# DAC.net
KiCad netlist of a schematic drawn in Altium Designer
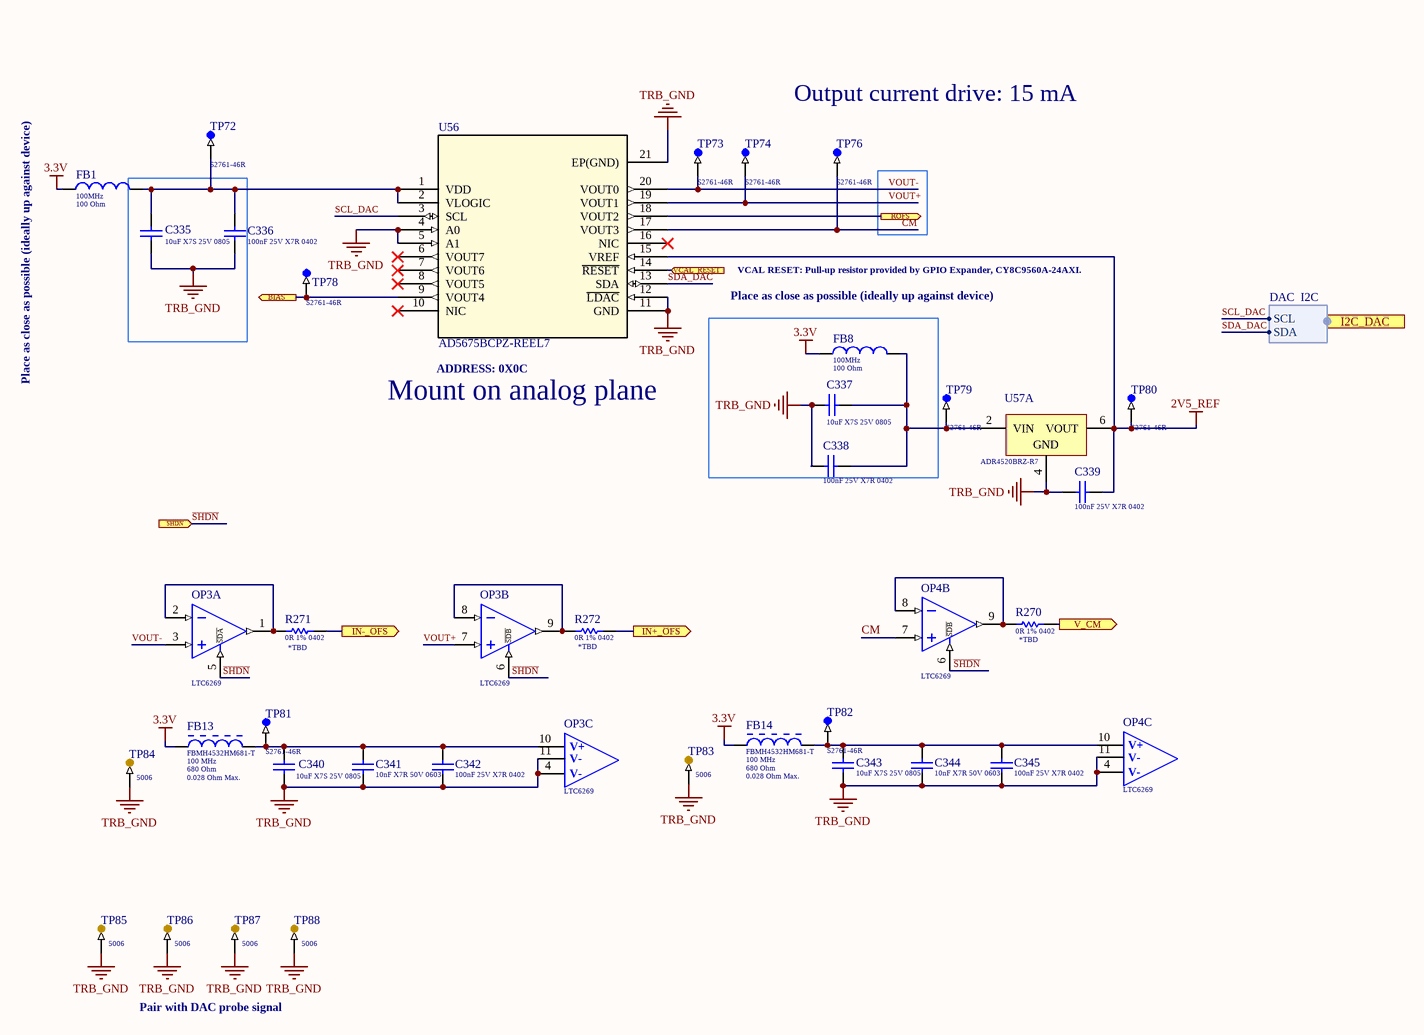
[diagram p0: DAC.SchDoc]

(export (version "E")
  (design (tool "Eeschema 10.0.6"))
  (components
    (comp (ref "C335")
      (value "Cap_Murata_ GRM21BC71E106ME11L_10uF")
      (footprint "Cap_Murata_ GRM21BC71E106ME11L_10uF")
      (description "CAP CER 10uF 25V X7R 0805")
      (fields (field (name "CAPACITANCE") "10uF X7S 25V 0805"))
      (libsource (lib "Cap_Murata_ GRM21BC71E106ME11L_10uF") (part "Cap_Murata_ GRM21BC71E106ME11L_10uF"))
    )
    (comp (ref "C336")
      (value "Cap_Taiyo_Yuden_TMK105B7104KV-FR_100nF")
      (footprint "Cap_Taiyo_Yuden_TMK105B7104KV-FR_100nF")
      (description "CAP CER 100nF 25V X7R 0402")
      (fields (field (name "CAPACITANCE") "100nF 25V X7R 0402"))
      (libsource (lib "Cap_Taiyo_Yuden_TMK105B7104KV-FR_100nF") (part "Cap_Taiyo_Yuden_TMK105B7104KV-FR_100nF"))
    )
    (comp (ref "C337")
      (value "Cap_Murata_ GRM21BC71E106ME11L_10uF")
      (footprint "Cap_Murata_ GRM21BC71E106ME11L_10uF")
      (description "CAP CER 10uF 25V X7R 0805")
      (fields (field (name "CAPACITANCE") "10uF X7S 25V 0805"))
      (libsource (lib "Cap_Murata_ GRM21BC71E106ME11L_10uF") (part "Cap_Murata_ GRM21BC71E106ME11L_10uF"))
    )
    (comp (ref "C338")
      (value "Cap_Taiyo_Yuden_TMK105B7104KV-FR_100nF")
      (footprint "Cap_Taiyo_Yuden_TMK105B7104KV-FR_100nF")
      (description "CAP CER 100nF 25V X7R 0402")
      (fields (field (name "CAPACITANCE") "100nF 25V X7R 0402"))
      (libsource (lib "Cap_Taiyo_Yuden_TMK105B7104KV-FR_100nF") (part "Cap_Taiyo_Yuden_TMK105B7104KV-FR_100nF"))
    )
    (comp (ref "C339")
      (value "Cap_Taiyo_Yuden_TMK105B7104KV-FR_100nF")
      (footprint "Cap_Taiyo_Yuden_TMK105B7104KV-FR_100nF")
      (description "CAP CER 100nF 25V X7R 0402")
      (fields (field (name "CAPACITANCE") "100nF 25V X7R 0402"))
      (libsource (lib "Cap_Taiyo_Yuden_TMK105B7104KV-FR_100nF") (part "Cap_Taiyo_Yuden_TMK105B7104KV-FR_100nF"))
    )
    (comp (ref "C340")
      (value "Cap_Murata_ GRM21BC71E106ME11L_10uF")
      (footprint "Cap_Murata_ GRM21BC71E106ME11L_10uF")
      (description "CAP CER 10uF 25V X7R 0805")
      (fields (field (name "CAPACITANCE") "10uF X7S 25V 0805"))
      (libsource (lib "Cap_Murata_ GRM21BC71E106ME11L_10uF") (part "Cap_Murata_ GRM21BC71E106ME11L_10uF"))
    )
    (comp (ref "C341")
      (value "Cap_Kemet_C0603C103J5RACTU_eec")
      (footprint "Kemet_C0603_0")
      (description "CAP CER 10nF 50V X7R 0603")
      (fields
        (field (name "PART NUMBER") "C0603C103J5RACTU")
        (field (name "MANUFACTURER") "Kemet")
        (field (name "CAPACITANCE") "10nF X7R 50V 0603")
      )
      (libsource (lib "Cap_Kemet_C0603C103J5RACTU_10nF") (part "Cap_Kemet_C0603C103J5RACTU_eec"))
    )
    (comp (ref "C342")
      (value "Cap_Taiyo_Yuden_TMK105B7104KV-FR_100nF")
      (footprint "Cap_Taiyo_Yuden_TMK105B7104KV-FR_100nF")
      (description "CAP CER 100nF 25V X7R 0402")
      (fields (field (name "CAPACITANCE") "100nF 25V X7R 0402"))
      (libsource (lib "Cap_Taiyo_Yuden_TMK105B7104KV-FR_100nF") (part "Cap_Taiyo_Yuden_TMK105B7104KV-FR_100nF"))
    )
    (comp (ref "C343")
      (value "Cap_Murata_ GRM21BC71E106ME11L_10uF")
      (footprint "Cap_Murata_ GRM21BC71E106ME11L_10uF")
      (description "CAP CER 10uF 25V X7R 0805")
      (fields (field (name "CAPACITANCE") "10uF X7S 25V 0805"))
      (libsource (lib "Cap_Murata_ GRM21BC71E106ME11L_10uF") (part "Cap_Murata_ GRM21BC71E106ME11L_10uF"))
    )
    (comp (ref "C344")
      (value "Cap_Kemet_C0603C103J5RACTU_eec")
      (footprint "Kemet_C0603_0")
      (description "CAP CER 10nF 50V X7R 0603")
      (fields
        (field (name "PART NUMBER") "C0603C103J5RACTU")
        (field (name "MANUFACTURER") "Kemet")
        (field (name "CAPACITANCE") "10nF X7R 50V 0603")
      )
      (libsource (lib "Cap_Kemet_C0603C103J5RACTU_10nF") (part "Cap_Kemet_C0603C103J5RACTU_eec"))
    )
    (comp (ref "C345")
      (value "Cap_Taiyo_Yuden_TMK105B7104KV-FR_100nF")
      (footprint "Cap_Taiyo_Yuden_TMK105B7104KV-FR_100nF")
      (description "CAP CER 100nF 25V X7R 0402")
      (fields (field (name "CAPACITANCE") "100nF 25V X7R 0402"))
      (libsource (lib "Cap_Taiyo_Yuden_TMK105B7104KV-FR_100nF") (part "Cap_Taiyo_Yuden_TMK105B7104KV-FR_100nF"))
    )
    (comp (ref "FB1")
      (value "742792731")
      (footprint "FB_Wurth_Electronics_742792731_100Ohms")
      (description "FB SMD 100 OHM 25% 1.2A 0402")
      (fields (field (name "MEASURING FREQUENCY") "100MHz") (field (name "IMPEDANCE") "100 Ohm"))
      (libsource (lib "FB_Wurth_Electronics_742792731_100Ohms") (part "FB_Wurth_Electronics_742792731_100Ohms"))
    )
    (comp (ref "FB8")
      (value "742792731")
      (footprint "FB_Wurth_Electronics_742792731_100Ohms")
      (description "FB SMD 100 OHM 25% 1.2A 0402")
      (fields (field (name "MEASURING FREQUENCY") "100MHz") (field (name "IMPEDANCE") "100 Ohm"))
      (libsource (lib "FB_Wurth_Electronics_742792731_100Ohms") (part "FB_Wurth_Electronics_742792731_100Ohms"))
    )
    (comp (ref "FB13")
      (value "FBMH4532HM681-T")
      (footprint "TAYO-FBMH4532-2_V")
      (fields
        (field (name "PARTNUMBER") "FBMH4532HM681-T")
        (field (name "MANUFACTURER") "Taiyo Yuden")
        (field (name "MEASURING FREQUENCY") "100 MHz")
        (field (name "NOMINAL IMPEDANCE") "680 Ohm")
        (field (name "DC RESISTANCE") "0.028 Ohm Max.")
      )
      (libsource (lib "Taiyo_Yuden_FBMH4532HM681") (part "FBMH4532HM681-T"))
    )
    (comp (ref "FB14")
      (value "FBMH4532HM681-T")
      (footprint "TAYO-FBMH4532-2_V")
      (fields
        (field (name "PARTNUMBER") "FBMH4532HM681-T")
        (field (name "MANUFACTURER") "Taiyo Yuden")
        (field (name "MEASURING FREQUENCY") "100 MHz")
        (field (name "NOMINAL IMPEDANCE") "680 Ohm")
        (field (name "DC RESISTANCE") "0.028 Ohm Max.")
      )
      (libsource (lib "Taiyo_Yuden_FBMH4532HM681") (part "FBMH4532HM681-T"))
    )
    (comp (ref "OP3")
      (value "OpAmp_Linear_Technology_ LTC6269HDD#PBF_500Mhz")
      (footprint "OpAmp_Linear_Technology_ LTC6269HDD#PBF_500Mhz")
      (description "IC OPAMP 500MHZ DUAL FET 10DFN")
      (fields (field (name "SERIES") "LTC6269"))
      (libsource (lib "OpAmp_Linear_Technology_ LTC6269HDD#PBF_500Mhz") (part "OpAmp_Linear_Technology_ LTC6269HDD#PBF_500Mhz"))
    )
    (comp (ref "OP4")
      (value "OpAmp_Linear_Technology_ LTC6269HDD#PBF_500Mhz")
      (footprint "OpAmp_Linear_Technology_ LTC6269HDD#PBF_500Mhz")
      (description "IC OPAMP 500MHZ DUAL FET 10DFN")
      (fields (field (name "SERIES") "LTC6269"))
      (libsource (lib "OpAmp_Linear_Technology_ LTC6269HDD#PBF_500Mhz") (part "OpAmp_Linear_Technology_ LTC6269HDD#PBF_500Mhz"))
    )
    (comp (ref "R270")
      (value "Res_Vishay_CRCW04020000Z0EDC_0_Ohm")
      (footprint "Res_Vishay_CRCW04020000Z0EDC_0_Ohm")
      (description "0R 0.062W 1% 0402 (1005 Metric)  SMD")
      (fields (field (name "RESISTANCE") "0R 1% 0402"))
      (libsource (lib "Res_Vishay_CRCW04020000Z0EDC_0_Ohm") (part "Res_Vishay_CRCW04020000Z0EDC_0_Ohm"))
    )
    (comp (ref "R271")
      (value "Res_Vishay_CRCW04020000Z0EDC_0_Ohm")
      (footprint "Res_Vishay_CRCW04020000Z0EDC_0_Ohm")
      (description "0R 0.062W 1% 0402 (1005 Metric)  SMD")
      (fields (field (name "RESISTANCE") "0R 1% 0402"))
      (libsource (lib "Res_Vishay_CRCW04020000Z0EDC_0_Ohm") (part "Res_Vishay_CRCW04020000Z0EDC_0_Ohm"))
    )
    (comp (ref "R272")
      (value "Res_Vishay_CRCW04020000Z0EDC_0_Ohm")
      (footprint "Res_Vishay_CRCW04020000Z0EDC_0_Ohm")
      (description "0R 0.062W 1% 0402 (1005 Metric)  SMD")
      (fields (field (name "RESISTANCE") "0R 1% 0402"))
      (libsource (lib "Res_Vishay_CRCW04020000Z0EDC_0_Ohm") (part "Res_Vishay_CRCW04020000Z0EDC_0_Ohm"))
    )
    (comp (ref "TP72")
      (value "TP_Harwin_S2761_46R")
      (footprint "TP_Harwin_S2761_46R")
      (description "Circuit Board Hardware - PCB SMT Mini Test Terminal, Reel")
      (fields (field (name "SERIES") "S2761-46R"))
      (libsource (lib "TP_Harwin_S2761_46R") (part "TP_Harwin_S2761_46R"))
    )
    (comp (ref "TP73")
      (value "TP_Harwin_S2761_46R")
      (footprint "TP_Harwin_S2761_46R")
      (description "Circuit Board Hardware - PCB SMT Mini Test Terminal, Reel")
      (fields (field (name "SERIES") "S2761-46R"))
      (libsource (lib "TP_Harwin_S2761_46R") (part "TP_Harwin_S2761_46R"))
    )
    (comp (ref "TP74")
      (value "TP_Harwin_S2761_46R")
      (footprint "TP_Harwin_S2761_46R")
      (description "Circuit Board Hardware - PCB SMT Mini Test Terminal, Reel")
      (fields (field (name "SERIES") "S2761-46R"))
      (libsource (lib "TP_Harwin_S2761_46R") (part "TP_Harwin_S2761_46R"))
    )
    (comp (ref "TP76")
      (value "TP_Harwin_S2761_46R")
      (footprint "TP_Harwin_S2761_46R")
      (description "Circuit Board Hardware - PCB SMT Mini Test Terminal, Reel")
      (fields (field (name "SERIES") "S2761-46R"))
      (libsource (lib "TP_Harwin_S2761_46R") (part "TP_Harwin_S2761_46R"))
    )
    (comp (ref "TP78")
      (value "TP_Harwin_S2761_46R")
      (footprint "TP_Harwin_S2761_46R")
      (description "Circuit Board Hardware - PCB SMT Mini Test Terminal, Reel")
      (fields (field (name "SERIES") "S2761-46R"))
      (libsource (lib "TP_Harwin_S2761_46R") (part "TP_Harwin_S2761_46R"))
    )
    (comp (ref "TP79")
      (value "TP_Harwin_S2761_46R")
      (footprint "TP_Harwin_S2761_46R")
      (description "Circuit Board Hardware - PCB SMT Mini Test Terminal, Reel")
      (fields (field (name "SERIES") "S2761-46R"))
      (libsource (lib "TP_Harwin_S2761_46R") (part "TP_Harwin_S2761_46R"))
    )
    (comp (ref "TP80")
      (value "TP_Harwin_S2761_46R")
      (footprint "TP_Harwin_S2761_46R")
      (description "Circuit Board Hardware - PCB SMT Mini Test Terminal, Reel")
      (fields (field (name "SERIES") "S2761-46R"))
      (libsource (lib "TP_Harwin_S2761_46R") (part "TP_Harwin_S2761_46R"))
    )
    (comp (ref "TP81")
      (value "TP_Harwin_S2761_46R")
      (footprint "TP_Harwin_S2761_46R")
      (description "Circuit Board Hardware - PCB SMT Mini Test Terminal, Reel")
      (fields (field (name "SERIES") "S2761-46R"))
      (libsource (lib "TP_Harwin_S2761_46R") (part "TP_Harwin_S2761_46R"))
    )
    (comp (ref "TP82")
      (value "TP_Harwin_S2761_46R")
      (footprint "TP_Harwin_S2761_46R")
      (description "Circuit Board Hardware - PCB SMT Mini Test Terminal, Reel")
      (fields (field (name "SERIES") "S2761-46R"))
      (libsource (lib "TP_Harwin_S2761_46R") (part "TP_Harwin_S2761_46R"))
    )
    (comp (ref "TP83")
      (value "TP_Keystone_Electronics_5006")
      (footprint "TP_Keystone_Electronics_5006")
      (description "Circuit Board Hardware - PCB TEST POINT BLK .063")
      (fields (field (name "SERIES") "5006"))
      (libsource (lib "TP_Keystone_Electronics_5006") (part "TP_Keystone_Electronics_5006"))
    )
    (comp (ref "TP84")
      (value "TP_Keystone_Electronics_5006")
      (footprint "TP_Keystone_Electronics_5006")
      (description "Circuit Board Hardware - PCB TEST POINT BLK .063")
      (fields (field (name "SERIES") "5006"))
      (libsource (lib "TP_Keystone_Electronics_5006") (part "TP_Keystone_Electronics_5006"))
    )
    (comp (ref "TP85")
      (value "TP_Keystone_Electronics_5006")
      (footprint "TP_Keystone_Electronics_5006")
      (description "Circuit Board Hardware - PCB TEST POINT BLK .063")
      (fields (field (name "SERIES") "5006"))
      (libsource (lib "TP_Keystone_Electronics_5006") (part "TP_Keystone_Electronics_5006"))
    )
    (comp (ref "TP86")
      (value "TP_Keystone_Electronics_5006")
      (footprint "TP_Keystone_Electronics_5006")
      (description "Circuit Board Hardware - PCB TEST POINT BLK .063")
      (fields (field (name "SERIES") "5006"))
      (libsource (lib "TP_Keystone_Electronics_5006") (part "TP_Keystone_Electronics_5006"))
    )
    (comp (ref "TP87")
      (value "TP_Keystone_Electronics_5006")
      (footprint "TP_Keystone_Electronics_5006")
      (description "Circuit Board Hardware - PCB TEST POINT BLK .063")
      (fields (field (name "SERIES") "5006"))
      (libsource (lib "TP_Keystone_Electronics_5006") (part "TP_Keystone_Electronics_5006"))
    )
    (comp (ref "TP88")
      (value "TP_Keystone_Electronics_5006")
      (footprint "TP_Keystone_Electronics_5006")
      (description "Circuit Board Hardware - PCB TEST POINT BLK .063")
      (fields (field (name "SERIES") "5006"))
      (libsource (lib "TP_Keystone_Electronics_5006") (part "TP_Keystone_Electronics_5006"))
    )
    (comp (ref "U56")
      (value "AD5675")
      (footprint "CP_20_8")
      (description "Digital to Analog Converters - DAC 16-bit octal I2C nanoDAC")
      (fields
        (field (name "MANUFACTURER_PART_NUMBER") "AD5675BCPZ-REEL7")
        (field (name "SERIES") "AD5675BCPZ-REEL7")
      )
      (libsource (lib "AD5675BCPZ-REEL7") (part "AD5675BCPZ-REEL7"))
    )
    (comp (ref "U57")
      (value "ADR4520BRZ-R7")
      (footprint "ADI-R-8_M")
      (fields (field (name "MANUFACTURER") "Analog Devices"))
      (libsource (lib "Altium Content Vault") (part "ADI-ADR45xx-R-8"))
    )
  )
  (nets
    (net (code "3") (name "/BIAS") (class "Default")
      (node (ref "TP78") (pin "1") (pinfunction "1_1") (pintype "input"))
      (node (ref "U56") (pin "9") (pinfunction "VOUT4_9") (pintype "output"))
    )
    (net (code "4") (name "/CM") (class "Default")
      (node (ref "OP4") (pin "7") (pinfunction "IN_A+_7") (pintype "input"))
      (node (ref "TP76") (pin "1") (pinfunction "1_1") (pintype "input"))
      (node (ref "U56") (pin "17") (pinfunction "VOUT3_17") (pintype "output"))
    )
    (net (code "5") (name "/IN+_OFS") (class "Default")
      (node (ref "R272") (pin "2") (pinfunction "2_2") (pintype "passive"))
    )
    (net (code "6") (name "/IN-_OFS") (class "Default")
      (node (ref "R271") (pin "2") (pinfunction "2_2") (pintype "passive"))
    )
    (net (code "7") (name "/ROFS") (class "Default")
      (node (ref "U56") (pin "18") (pinfunction "VOUT2_18") (pintype "output"))
    )
    (net (code "8") (name "/SCL_DAC") (class "Default")
      (node (ref "U56") (pin "3") (pinfunction "SCL_3") (pintype "bidirectional"))
    )
    (net (code "9") (name "/SDA_DAC") (class "Default")
      (node (ref "U56") (pin "13") (pinfunction "SDA_13") (pintype "bidirectional"))
    )
    (net (code "10") (name "/VCAL_RESET") (class "Default")
      (node (ref "U56") (pin "14") (pinfunction "~{RESET}_14") (pintype "input"))
    )
    (net (code "11") (name "/VOUT+") (class "Default")
      (node (ref "OP3") (pin "7") (pinfunction "IN_A+_7") (pintype "input"))
      (node (ref "TP74") (pin "1") (pinfunction "1_1") (pintype "input"))
      (node (ref "U56") (pin "19") (pinfunction "VOUT1_19") (pintype "output"))
    )
    (net (code "12") (name "/VOUT-") (class "Default")
      (node (ref "OP3") (pin "3") (pinfunction "IN_A+_3") (pintype "input"))
      (node (ref "TP73") (pin "1") (pinfunction "1_1") (pintype "input"))
      (node (ref "U56") (pin "20") (pinfunction "VOUT0_20") (pintype "output"))
    )
    (net (code "13") (name "/V_CM") (class "Default")
      (node (ref "R270") (pin "2") (pinfunction "2_2") (pintype "passive"))
    )
    (net (code "15") (name "/~{SHDN}") (class "Default")
      (node (ref "OP3") (pin "5") (pinfunction "~{SDA}_5") (pintype "input"))
      (node (ref "OP3") (pin "6") (pinfunction "~{SDB}_6") (pintype "input"))
      (node (ref "OP4") (pin "6") (pinfunction "~{SDB}_6") (pintype "input"))
    )
    (net (code "16") (name "2V5_REF") (class "Default")
      (node (ref "C339") (pin "2") (pinfunction "2_2") (pintype "passive"))
      (node (ref "TP80") (pin "1") (pinfunction "1_1") (pintype "input"))
      (node (ref "U56") (pin "15") (pinfunction "VREF_15") (pintype "input"))
      (node (ref "U57") (pin "6") (pinfunction "VOUT_6") (pintype "power_in"))
    )
    (net (code "17") (name "3.3V") (class "Default")
      (node (ref "FB1") (pin "1") (pinfunction "1_1") (pintype "passive"))
      (node (ref "FB13") (pin "1") (pinfunction "1_1") (pintype "passive"))
      (node (ref "FB14") (pin "1") (pinfunction "1_1") (pintype "passive"))
      (node (ref "FB8") (pin "1") (pinfunction "1_1") (pintype "passive"))
    )
    (net (code "18") (name "Net-(OP3A-IN_A-)") (class "Default")
      (node (ref "OP3") (pin "1") (pinfunction "OUT_A_1") (pintype "output"))
      (node (ref "OP3") (pin "2") (pinfunction "IN_A-_2") (pintype "input"))
      (node (ref "R271") (pin "1") (pinfunction "1_1") (pintype "passive"))
    )
    (net (code "19") (name "Net-(OP3B-IN_A-)") (class "Default")
      (node (ref "OP3") (pin "8") (pinfunction "IN_A-_8") (pintype "input"))
      (node (ref "OP3") (pin "9") (pinfunction "OUT_A_9") (pintype "output"))
      (node (ref "R272") (pin "1") (pinfunction "1_1") (pintype "passive"))
    )
    (net (code "20") (name "Net-(OP3C-V+)") (class "Default")
      (node (ref "C340") (pin "1") (pinfunction "1_1") (pintype "passive"))
      (node (ref "C341") (pin "1") (pinfunction "1_1") (pintype "passive"))
      (node (ref "C342") (pin "2") (pinfunction "2_2") (pintype "passive"))
      (node (ref "FB13") (pin "2") (pinfunction "2_2") (pintype "passive"))
      (node (ref "OP3") (pin "10") (pinfunction "V+_10") (pintype "power_in"))
      (node (ref "TP81") (pin "1") (pinfunction "1_1") (pintype "input"))
    )
    (net (code "21") (name "Net-(OP4B-IN_A-)") (class "Default")
      (node (ref "OP4") (pin "8") (pinfunction "IN_A-_8") (pintype "input"))
      (node (ref "OP4") (pin "9") (pinfunction "OUT_A_9") (pintype "output"))
      (node (ref "R270") (pin "1") (pinfunction "1_1") (pintype "passive"))
    )
    (net (code "22") (name "Net-(OP4C-V+)") (class "Default")
      (node (ref "C343") (pin "1") (pinfunction "1_1") (pintype "passive"))
      (node (ref "C344") (pin "1") (pinfunction "1_1") (pintype "passive"))
      (node (ref "C345") (pin "2") (pinfunction "2_2") (pintype "passive"))
      (node (ref "FB14") (pin "2") (pinfunction "2_2") (pintype "passive"))
      (node (ref "OP4") (pin "10") (pinfunction "V+_10") (pintype "power_in"))
      (node (ref "TP82") (pin "1") (pinfunction "1_1") (pintype "input"))
    )
    (net (code "23") (name "Net-(U56-VDD)") (class "Default")
      (node (ref "C335") (pin "1") (pinfunction "1_1") (pintype "passive"))
      (node (ref "C336") (pin "2") (pinfunction "2_2") (pintype "passive"))
      (node (ref "FB1") (pin "2") (pinfunction "2_2") (pintype "passive"))
      (node (ref "TP72") (pin "1") (pinfunction "1_1") (pintype "input"))
      (node (ref "U56") (pin "1") (pinfunction "VDD_1") (pintype "power_in"))
      (node (ref "U56") (pin "2") (pinfunction "VLOGIC_2") (pintype "power_in"))
    )
    (net (code "24") (name "Net-(U57A-VIN)") (class "Default")
      (node (ref "C337") (pin "1") (pinfunction "1_1") (pintype "passive"))
      (node (ref "C338") (pin "2") (pinfunction "2_2") (pintype "passive"))
      (node (ref "FB8") (pin "2") (pinfunction "2_2") (pintype "passive"))
      (node (ref "TP79") (pin "1") (pinfunction "1_1") (pintype "input"))
      (node (ref "U57") (pin "2") (pinfunction "VIN_2") (pintype "power_in"))
    )
    (net (code "25") (name "TRB_GND") (class "Default")
      (node (ref "C335") (pin "2") (pinfunction "2_2") (pintype "passive"))
      (node (ref "C336") (pin "1") (pinfunction "1_1") (pintype "passive"))
      (node (ref "C337") (pin "2") (pinfunction "2_2") (pintype "passive"))
      (node (ref "C338") (pin "1") (pinfunction "1_1") (pintype "passive"))
      (node (ref "C339") (pin "1") (pinfunction "1_1") (pintype "passive"))
      (node (ref "C340") (pin "2") (pinfunction "2_2") (pintype "passive"))
      (node (ref "C341") (pin "2") (pinfunction "2_2") (pintype "passive"))
      (node (ref "C342") (pin "1") (pinfunction "1_1") (pintype "passive"))
      (node (ref "C343") (pin "2") (pinfunction "2_2") (pintype "passive"))
      (node (ref "C344") (pin "2") (pinfunction "2_2") (pintype "passive"))
      (node (ref "C345") (pin "1") (pinfunction "1_1") (pintype "passive"))
      (node (ref "OP3") (pin "11") (pinfunction "V-_11") (pintype "power_in"))
      (node (ref "OP3") (pin "4") (pinfunction "V-_4") (pintype "power_in"))
      (node (ref "OP4") (pin "11") (pinfunction "V-_11") (pintype "power_in"))
      (node (ref "OP4") (pin "4") (pinfunction "V-_4") (pintype "power_in"))
      (node (ref "TP83") (pin "1") (pinfunction "1_1") (pintype "input"))
      (node (ref "TP84") (pin "1") (pinfunction "1_1") (pintype "input"))
      (node (ref "TP85") (pin "1") (pinfunction "1_1") (pintype "input"))
      (node (ref "TP86") (pin "1") (pinfunction "1_1") (pintype "input"))
      (node (ref "TP87") (pin "1") (pinfunction "1_1") (pintype "input"))
      (node (ref "TP88") (pin "1") (pinfunction "1_1") (pintype "input"))
      (node (ref "U56") (pin "11") (pinfunction "GND_11") (pintype "passive"))
      (node (ref "U56") (pin "12") (pinfunction "~{LDAC}_12") (pintype "input"))
      (node (ref "U56") (pin "21") (pinfunction "EP(GND)_21") (pintype "passive"))
      (node (ref "U56") (pin "4") (pinfunction "A0_4") (pintype "input"))
      (node (ref "U56") (pin "5") (pinfunction "A1_5") (pintype "input"))
      (node (ref "U57") (pin "4") (pinfunction "GND_4") (pintype "power_in"))
    )
    (net (code "26") (name "unconnected-(U56-NIC-Pad10)") (class "Default")
      (node (ref "U56") (pin "10") (pinfunction "NIC_10") (pintype "passive+no_connect"))
    )
    (net (code "27") (name "unconnected-(U56-NIC-Pad16)") (class "Default")
      (node (ref "U56") (pin "16") (pinfunction "NIC_16") (pintype "passive+no_connect"))
    )
    (net (code "28") (name "unconnected-(U56-VOUT5-Pad8)") (class "Default")
      (node (ref "U56") (pin "8") (pinfunction "VOUT5_8") (pintype "output+no_connect"))
    )
    (net (code "29") (name "unconnected-(U56-VOUT6-Pad7)") (class "Default")
      (node (ref "U56") (pin "7") (pinfunction "VOUT6_7") (pintype "output+no_connect"))
    )
    (net (code "30") (name "unconnected-(U56-VOUT7-Pad6)") (class "Default")
      (node (ref "U56") (pin "6") (pinfunction "VOUT7_6") (pintype "output+no_connect"))
    )
  )
)
